# CAN_Module.net
KiCad netlist of a schematic drawn in EAGLE
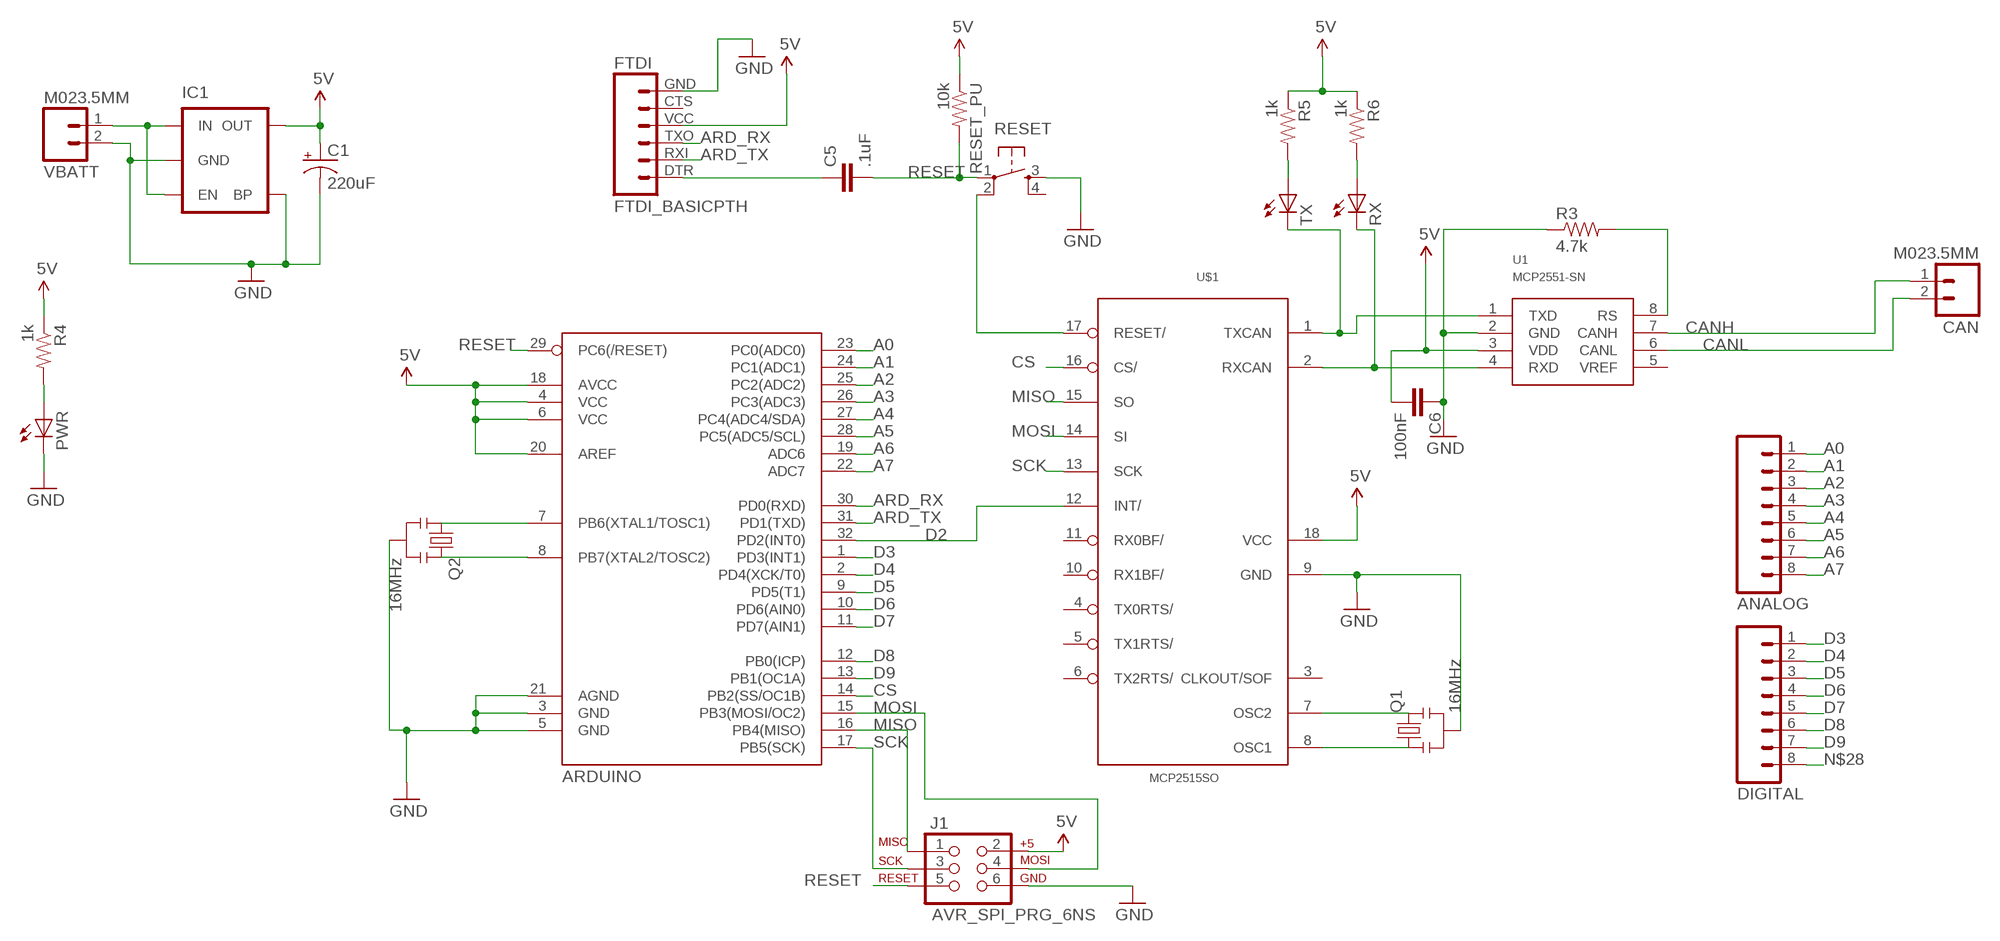
[diagram p0: schematic, sheet 1]

(export (version "E")
  (design (tool "Eeschema 10.0.6"))
  (components
    (comp (ref "ANALOG")
      (value "M08LOCK")
      (footprint "eagle-import:1X08_LOCK")
      (libsource (lib "eagle-import") (part "M08LOCK"))
    )
    (comp (ref "ARDUINO")
      (value "ATMEGA328_SMT")
      (footprint "eagle-import:TQFP32-08")
      (libsource (lib "eagle-import") (part "ATMEGA328_SMT"))
    )
    (comp (ref "C1")
      (value "220uF")
      (footprint "eagle-import:EIA3216-KIT")
      (libsource (lib "eagle-import") (part "CAP_POL1206-KIT"))
    )
    (comp (ref "C5")
      (value ".1uF")
      (footprint "eagle-import:0805")
      (libsource (lib "eagle-import") (part "CAP0805"))
    )
    (comp (ref "C6")
      (value "100nF")
      (footprint "eagle-import:0805")
      (libsource (lib "eagle-import") (part "CAP0805"))
    )
    (comp (ref "CAN")
      (value "M023.5MM")
      (footprint "eagle-import:SCREWTERMINAL-3.5MM-2")
      (libsource (lib "eagle-import") (part "M023.5MM"))
    )
    (comp (ref "DIGITAL")
      (value "M08LOCK")
      (footprint "eagle-import:1X08_LOCK")
      (libsource (lib "eagle-import") (part "M08LOCK"))
    )
    (comp (ref "FTDI")
      (value "FTDI_BASICPTH")
      (footprint "eagle-import:FTDI_BASIC")
      (libsource (lib "eagle-import") (part "FTDI_BASICPTH"))
    )
    (comp (ref "IC1")
      (value "MIC52055V")
      (footprint "eagle-import:SOT23-5")
      (libsource (lib "eagle-import") (part "MIC52055V"))
    )
    (comp (ref "J1")
      (value "AVR_SPI_PRG_6NS")
      (footprint "eagle-import:2X3-NS")
      (libsource (lib "eagle-import") (part "AVR_SPI_PRG_6NS"))
    )
    (comp (ref "PWR")
      (value "LEDCHIPLED_0805")
      (footprint "eagle-import:CHIPLED_0805")
      (libsource (lib "eagle-import") (part "LEDCHIPLED_0805"))
    )
    (comp (ref "Q1")
      (value "16MHz")
      (footprint "eagle-import:RESONATOR-SMD")
      (libsource (lib "eagle-import") (part "RESONATOR16MHZ"))
    )
    (comp (ref "Q2")
      (value "16MHz")
      (footprint "eagle-import:RESONATOR-SMD")
      (libsource (lib "eagle-import") (part "RESONATOR16MHZ"))
    )
    (comp (ref "R3")
      (value "4.7k")
      (footprint "eagle-import:0805")
      (libsource (lib "eagle-import") (part "RESISTOR0805-RES"))
    )
    (comp (ref "R4")
      (value "1k")
      (footprint "eagle-import:0805")
      (libsource (lib "eagle-import") (part "RESISTOR0805-RES"))
    )
    (comp (ref "R5")
      (value "1k")
      (footprint "eagle-import:0805")
      (libsource (lib "eagle-import") (part "RESISTOR0805-RES"))
    )
    (comp (ref "R6")
      (value "1k")
      (footprint "eagle-import:0805")
      (libsource (lib "eagle-import") (part "RESISTOR0805-RES"))
    )
    (comp (ref "RESET")
      (value "TAC_SWITCHSMD")
      (footprint "eagle-import:TACTILE_SWITCH_SMD")
      (libsource (lib "eagle-import") (part "TAC_SWITCHSMD"))
    )
    (comp (ref "RESET_PU")
      (value "10k")
      (footprint "eagle-import:0805")
      (libsource (lib "eagle-import") (part "RESISTOR0805-RES"))
    )
    (comp (ref "RX")
      (value "LEDCHIPLED_0805")
      (footprint "eagle-import:CHIPLED_0805")
      (libsource (lib "eagle-import") (part "LEDCHIPLED_0805"))
    )
    (comp (ref "TX")
      (value "LEDCHIPLED_0805")
      (footprint "eagle-import:CHIPLED_0805")
      (libsource (lib "eagle-import") (part "LEDCHIPLED_0805"))
    )
    (comp (ref "U$1")
      (value "MCP2515SO")
      (footprint "eagle-import:SO18L")
      (libsource (lib "eagle-import") (part "MCP2515SO"))
    )
    (comp (ref "U1")
      (value "MCP2551-SN")
      (footprint "eagle-import:SO-08")
      (libsource (lib "eagle-import") (part "MCP2551-SN"))
    )
    (comp (ref "VBATT")
      (value "M023.5MM")
      (footprint "eagle-import:SCREWTERMINAL-3.5MM-2")
      (libsource (lib "eagle-import") (part "M023.5MM"))
    )
  )
  (nets
    (net (code "1") (name "/A0") (class "Default")
      (node (ref "ANALOG") (pin "1") (pinfunction "1_1") (pintype "passive"))
      (node (ref "ARDUINO") (pin "23") (pinfunction "PC0(ADC0)_23") (pintype "bidirectional"))
    )
    (net (code "2") (name "/A1") (class "Default")
      (node (ref "ANALOG") (pin "2") (pinfunction "2_2") (pintype "passive"))
      (node (ref "ARDUINO") (pin "24") (pinfunction "PC1(ADC1)_24") (pintype "bidirectional"))
    )
    (net (code "3") (name "/A2") (class "Default")
      (node (ref "ANALOG") (pin "3") (pinfunction "3_3") (pintype "passive"))
      (node (ref "ARDUINO") (pin "25") (pinfunction "PC2(ADC2)_25") (pintype "bidirectional"))
    )
    (net (code "4") (name "/A3") (class "Default")
      (node (ref "ANALOG") (pin "4") (pinfunction "4_4") (pintype "passive"))
      (node (ref "ARDUINO") (pin "26") (pinfunction "PC3(ADC3)_26") (pintype "bidirectional"))
    )
    (net (code "5") (name "/A4") (class "Default")
      (node (ref "ANALOG") (pin "5") (pinfunction "5_5") (pintype "passive"))
      (node (ref "ARDUINO") (pin "27") (pinfunction "PC4(ADC4/SDA)_27") (pintype "bidirectional"))
    )
    (net (code "6") (name "/A5") (class "Default")
      (node (ref "ANALOG") (pin "6") (pinfunction "6_6") (pintype "passive"))
      (node (ref "ARDUINO") (pin "28") (pinfunction "PC5(ADC5/SCL)_28") (pintype "bidirectional"))
    )
    (net (code "7") (name "/A6") (class "Default")
      (node (ref "ANALOG") (pin "7") (pinfunction "7_7") (pintype "passive"))
      (node (ref "ARDUINO") (pin "19") (pinfunction "ADC6_19") (pintype "bidirectional"))
    )
    (net (code "8") (name "/A7") (class "Default")
      (node (ref "ANALOG") (pin "8") (pinfunction "8_8") (pintype "passive"))
      (node (ref "ARDUINO") (pin "22") (pinfunction "ADC7_22") (pintype "bidirectional"))
    )
    (net (code "9") (name "/ARD_RX") (class "Default")
      (node (ref "ARDUINO") (pin "30") (pinfunction "PD0(RXD)_30") (pintype "bidirectional"))
      (node (ref "FTDI") (pin "TXO") (pinfunction "3_TXO") (pintype "passive"))
    )
    (net (code "10") (name "/ARD_TX") (class "Default")
      (node (ref "ARDUINO") (pin "31") (pinfunction "PD1(TXD)_31") (pintype "bidirectional"))
      (node (ref "FTDI") (pin "RXI") (pinfunction "2_RXI") (pintype "passive"))
    )
    (net (code "11") (name "/CANH") (class "Default")
      (node (ref "CAN") (pin "1") (pinfunction "1_1") (pintype "passive"))
      (node (ref "U1") (pin "7") (pinfunction "CANH_7") (pintype "bidirectional"))
    )
    (net (code "12") (name "/CANL") (class "Default")
      (node (ref "CAN") (pin "2") (pinfunction "2_2") (pintype "passive"))
      (node (ref "U1") (pin "6") (pinfunction "CANL_6") (pintype "bidirectional"))
    )
    (net (code "13") (name "/CS") (class "Default")
      (node (ref "ARDUINO") (pin "14") (pinfunction "PB2(SS/OC1B)_14") (pintype "bidirectional"))
      (node (ref "U$1") (pin "16") (pinfunction "CS/_16") (pintype "input"))
    )
    (net (code "14") (name "/D2") (class "Default")
      (node (ref "ARDUINO") (pin "32") (pinfunction "PD2(INT0)_32") (pintype "bidirectional"))
      (node (ref "U$1") (pin "12") (pinfunction "INT/_12") (pintype "output"))
    )
    (net (code "15") (name "/D3") (class "Default")
      (node (ref "ARDUINO") (pin "1") (pinfunction "PD3(INT1)_1") (pintype "bidirectional"))
      (node (ref "DIGITAL") (pin "1") (pinfunction "1_1") (pintype "passive"))
    )
    (net (code "16") (name "/D4") (class "Default")
      (node (ref "ARDUINO") (pin "2") (pinfunction "PD4(XCK/T0)_2") (pintype "bidirectional"))
      (node (ref "DIGITAL") (pin "2") (pinfunction "2_2") (pintype "passive"))
    )
    (net (code "17") (name "/D5") (class "Default")
      (node (ref "ARDUINO") (pin "9") (pinfunction "PD5(T1)_9") (pintype "bidirectional"))
      (node (ref "DIGITAL") (pin "3") (pinfunction "3_3") (pintype "passive"))
    )
    (net (code "18") (name "/D6") (class "Default")
      (node (ref "ARDUINO") (pin "10") (pinfunction "PD6(AIN0)_10") (pintype "bidirectional"))
      (node (ref "DIGITAL") (pin "4") (pinfunction "4_4") (pintype "passive"))
    )
    (net (code "19") (name "/D7") (class "Default")
      (node (ref "ARDUINO") (pin "11") (pinfunction "PD7(AIN1)_11") (pintype "bidirectional"))
      (node (ref "DIGITAL") (pin "5") (pinfunction "5_5") (pintype "passive"))
    )
    (net (code "20") (name "/D8") (class "Default")
      (node (ref "ARDUINO") (pin "12") (pinfunction "PB0(ICP)_12") (pintype "bidirectional"))
      (node (ref "DIGITAL") (pin "6") (pinfunction "6_6") (pintype "passive"))
    )
    (net (code "21") (name "/D9") (class "Default")
      (node (ref "ARDUINO") (pin "13") (pinfunction "PB1(OC1A)_13") (pintype "bidirectional"))
      (node (ref "DIGITAL") (pin "7") (pinfunction "7_7") (pintype "passive"))
    )
    (net (code "22") (name "/MISO") (class "Default")
      (node (ref "ARDUINO") (pin "16") (pinfunction "PB4(MISO)_16") (pintype "bidirectional"))
      (node (ref "J1") (pin "1") (pinfunction "1_1") (pintype "passive"))
      (node (ref "U$1") (pin "15") (pinfunction "SO_15") (pintype "output"))
    )
    (net (code "23") (name "/MOSI") (class "Default")
      (node (ref "ARDUINO") (pin "15") (pinfunction "PB3(MOSI/OC2)_15") (pintype "bidirectional"))
      (node (ref "J1") (pin "4") (pinfunction "4_4") (pintype "passive"))
      (node (ref "U$1") (pin "14") (pinfunction "SI_14") (pintype "input"))
    )
    (net (code "24") (name "/N$28") (class "Default")
      (node (ref "DIGITAL") (pin "8") (pinfunction "8_8") (pintype "passive"))
    )
    (net (code "25") (name "/RESET") (class "Default")
      (node (ref "ARDUINO") (pin "29") (pinfunction "PC6(/RESET)_29") (pintype "bidirectional"))
      (node (ref "C5") (pin "2") (pinfunction "2_2") (pintype "passive"))
      (node (ref "J1") (pin "5") (pinfunction "5_5") (pintype "passive"))
      (node (ref "RESET") (pin "1") (pinfunction "1_1") (pintype "passive"))
      (node (ref "RESET_PU") (pin "2") (pinfunction "2_2") (pintype "passive"))
    )
    (net (code "26") (name "/SCK") (class "Default")
      (node (ref "ARDUINO") (pin "17") (pinfunction "PB5(SCK)_17") (pintype "bidirectional"))
      (node (ref "J1") (pin "3") (pinfunction "3_3") (pintype "passive"))
      (node (ref "U$1") (pin "13") (pinfunction "SCK_13") (pintype "input"))
    )
    (net (code "27") (name "5V") (class "Default")
      (node (ref "ARDUINO") (pin "18") (pinfunction "AVCC_18") (pintype "bidirectional"))
      (node (ref "ARDUINO") (pin "20") (pinfunction "AREF_20") (pintype "bidirectional"))
      (node (ref "ARDUINO") (pin "4") (pinfunction "VCC_4") (pintype "bidirectional"))
      (node (ref "ARDUINO") (pin "6") (pinfunction "VCC_6") (pintype "bidirectional"))
      (node (ref "C1") (pin "A") (pinfunction "+_A") (pintype "passive"))
      (node (ref "C6") (pin "2") (pinfunction "2_2") (pintype "passive"))
      (node (ref "FTDI") (pin "VCC") (pinfunction "4_VCC") (pintype "passive"))
      (node (ref "IC1") (pin "5") (pinfunction "OUT_5") (pintype "passive"))
      (node (ref "J1") (pin "2") (pinfunction "2_2") (pintype "passive"))
      (node (ref "R4") (pin "1") (pinfunction "1_1") (pintype "passive"))
      (node (ref "R5") (pin "1") (pinfunction "1_1") (pintype "passive"))
      (node (ref "R6") (pin "1") (pinfunction "1_1") (pintype "passive"))
      (node (ref "RESET_PU") (pin "1") (pinfunction "1_1") (pintype "passive"))
      (node (ref "U$1") (pin "18") (pinfunction "VCC_18") (pintype "power_in"))
      (node (ref "U1") (pin "3") (pinfunction "VDD_3") (pintype "power_in"))
    )
    (net (code "28") (name "GND") (class "Default")
      (node (ref "ARDUINO") (pin "21") (pinfunction "AGND_21") (pintype "bidirectional"))
      (node (ref "ARDUINO") (pin "3") (pinfunction "GND_3") (pintype "bidirectional"))
      (node (ref "ARDUINO") (pin "5") (pinfunction "GND_5") (pintype "bidirectional"))
      (node (ref "C1") (pin "C") (pinfunction "-_C") (pintype "passive"))
      (node (ref "C6") (pin "1") (pinfunction "1_1") (pintype "passive"))
      (node (ref "FTDI") (pin "GND") (pinfunction "6_GND") (pintype "passive"))
      (node (ref "IC1") (pin "2") (pinfunction "GND_2") (pintype "input"))
      (node (ref "IC1") (pin "4") (pinfunction "BP_4") (pintype "input"))
      (node (ref "J1") (pin "6") (pinfunction "6_6") (pintype "passive"))
      (node (ref "PWR") (pin "C") (pinfunction "C_C") (pintype "passive"))
      (node (ref "Q1") (pin "2") (pinfunction "2_2") (pintype "passive"))
      (node (ref "Q2") (pin "2") (pinfunction "2_2") (pintype "passive"))
      (node (ref "R3") (pin "1") (pinfunction "1_1") (pintype "passive"))
      (node (ref "RESET") (pin "3") (pinfunction "3_3") (pintype "passive"))
      (node (ref "U$1") (pin "9") (pinfunction "GND_9") (pintype "power_in"))
      (node (ref "U1") (pin "2") (pinfunction "GND_2") (pintype "power_in"))
      (node (ref "VBATT") (pin "2") (pinfunction "2_2") (pintype "passive"))
    )
    (net (code "29") (name "Net-(ARDUINO-PB6(XTAL1{slash}TOSC1))") (class "Default")
      (node (ref "ARDUINO") (pin "7") (pinfunction "PB6(XTAL1/TOSC1)_7") (pintype "bidirectional"))
      (node (ref "Q2") (pin "1") (pinfunction "1_1") (pintype "passive"))
    )
    (net (code "30") (name "Net-(ARDUINO-PB7(XTAL2{slash}TOSC2))") (class "Default")
      (node (ref "ARDUINO") (pin "8") (pinfunction "PB7(XTAL2/TOSC2)_8") (pintype "bidirectional"))
      (node (ref "Q2") (pin "3") (pinfunction "3_3") (pintype "passive"))
    )
    (net (code "31") (name "Net-(FTDI-1)") (class "Default")
      (node (ref "C5") (pin "1") (pinfunction "1_1") (pintype "passive"))
      (node (ref "FTDI") (pin "DTR") (pinfunction "1_DTR") (pintype "passive"))
    )
    (net (code "32") (name "Net-(IC1-EN)") (class "Default")
      (node (ref "IC1") (pin "1") (pinfunction "IN_1") (pintype "input"))
      (node (ref "IC1") (pin "3") (pinfunction "EN_3") (pintype "input"))
      (node (ref "VBATT") (pin "1") (pinfunction "1_1") (pintype "passive"))
    )
    (net (code "33") (name "Net-(PWR-PadA)") (class "Default")
      (node (ref "PWR") (pin "A") (pinfunction "A_A") (pintype "passive"))
      (node (ref "R4") (pin "2") (pinfunction "2_2") (pintype "passive"))
    )
    (net (code "34") (name "Net-(R5-Pad2)") (class "Default")
      (node (ref "R5") (pin "2") (pinfunction "2_2") (pintype "passive"))
      (node (ref "TX") (pin "A") (pinfunction "A_A") (pintype "passive"))
    )
    (net (code "35") (name "Net-(R6-Pad2)") (class "Default")
      (node (ref "R6") (pin "2") (pinfunction "2_2") (pintype "passive"))
      (node (ref "RX") (pin "A") (pinfunction "A_A") (pintype "passive"))
    )
    (net (code "36") (name "Net-(U$1-OSC1)") (class "Default")
      (node (ref "Q1") (pin "1") (pinfunction "1_1") (pintype "passive"))
      (node (ref "U$1") (pin "8") (pinfunction "OSC1_8") (pintype "bidirectional"))
    )
    (net (code "37") (name "Net-(U$1-OSC2)") (class "Default")
      (node (ref "Q1") (pin "3") (pinfunction "3_3") (pintype "passive"))
      (node (ref "U$1") (pin "7") (pinfunction "OSC2_7") (pintype "bidirectional"))
    )
    (net (code "38") (name "Net-(U$1-RESET{slash})") (class "Default")
      (node (ref "RESET") (pin "2") (pinfunction "2_2") (pintype "passive"))
      (node (ref "U$1") (pin "17") (pinfunction "RESET/_17") (pintype "input"))
    )
    (net (code "39") (name "Net-(U$1-RXCAN)") (class "Default")
      (node (ref "RX") (pin "C") (pinfunction "C_C") (pintype "passive"))
      (node (ref "U$1") (pin "2") (pinfunction "RXCAN_2") (pintype "input"))
      (node (ref "U1") (pin "4") (pinfunction "RXD_4") (pintype "input"))
    )
    (net (code "40") (name "Net-(U$1-TXCAN)") (class "Default")
      (node (ref "TX") (pin "C") (pinfunction "C_C") (pintype "passive"))
      (node (ref "U$1") (pin "1") (pinfunction "TXCAN_1") (pintype "output"))
      (node (ref "U1") (pin "1") (pinfunction "TXD_1") (pintype "output"))
    )
    (net (code "41") (name "Net-(U1-RS)") (class "Default")
      (node (ref "R3") (pin "2") (pinfunction "2_2") (pintype "passive"))
      (node (ref "U1") (pin "8") (pinfunction "RS_8") (pintype "output"))
    )
    (net (code "42") (name "unconnected-(FTDI-5-PadCTS)") (class "Default")
      (node (ref "FTDI") (pin "CTS") (pinfunction "5_CTS") (pintype "passive"))
    )
    (net (code "43") (name "unconnected-(RESET-Pad4)") (class "Default")
      (node (ref "RESET") (pin "4") (pinfunction "4_4") (pintype "passive"))
    )
    (net (code "44") (name "unconnected-(U$1-CLKOUT{slash}SOF-Pad3)") (class "Default")
      (node (ref "U$1") (pin "3") (pinfunction "CLKOUT/SOF_3") (pintype "bidirectional"))
    )
    (net (code "45") (name "unconnected-(U$1-RX0BF{slash}-Pad11)") (class "Default")
      (node (ref "U$1") (pin "11") (pinfunction "RX0BF/_11") (pintype "bidirectional"))
    )
    (net (code "46") (name "unconnected-(U$1-RX1BF{slash}-Pad10)") (class "Default")
      (node (ref "U$1") (pin "10") (pinfunction "RX1BF/_10") (pintype "bidirectional"))
    )
    (net (code "47") (name "unconnected-(U$1-TX0RTS{slash}-Pad4)") (class "Default")
      (node (ref "U$1") (pin "4") (pinfunction "TX0RTS/_4") (pintype "bidirectional"))
    )
    (net (code "48") (name "unconnected-(U$1-TX1RTS{slash}-Pad5)") (class "Default")
      (node (ref "U$1") (pin "5") (pinfunction "TX1RTS/_5") (pintype "bidirectional"))
    )
    (net (code "49") (name "unconnected-(U$1-TX2RTS{slash}-Pad6)") (class "Default")
      (node (ref "U$1") (pin "6") (pinfunction "TX2RTS/_6") (pintype "bidirectional"))
    )
    (net (code "50") (name "unconnected-(U1-VREF-Pad5)") (class "Default")
      (node (ref "U1") (pin "5") (pinfunction "VREF_5") (pintype "output"))
    )
  )
)
